# openSX70_SCHEMATIC_COMPLETE.net
KiCad netlist of a schematic drawn in EAGLE
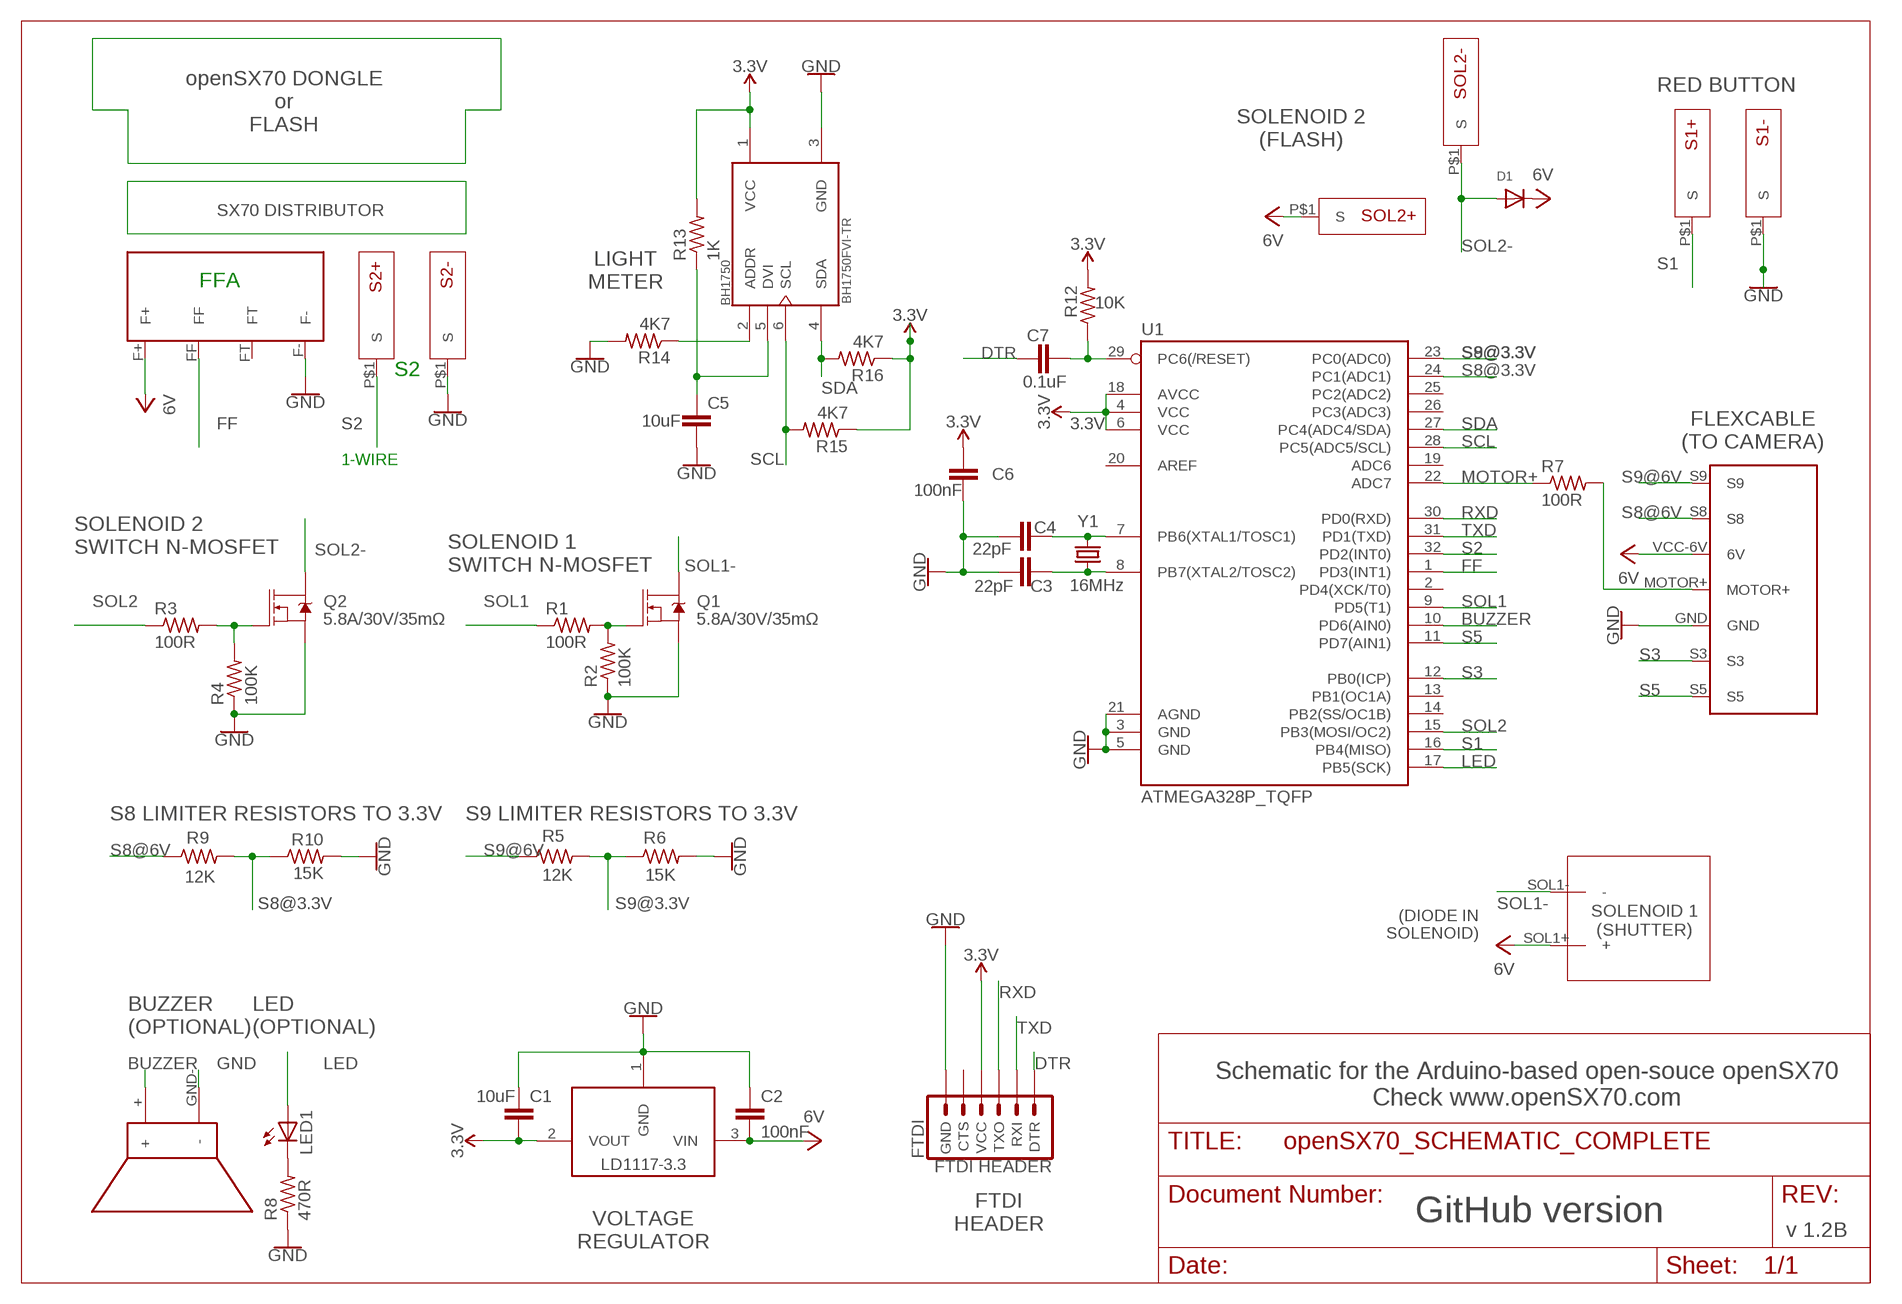
[diagram p0: schematic, sheet 1]

(export (version "E")
  (design (tool "Eeschema 10.0.6"))
  (components
    (comp (ref "BH1750")
      (value "BH1750FVI-TR")
      (footprint "eagle-import:SOTFL50P300X75-6N")
      (fields (field (name "MF") "Rohm"))
      (libsource (lib "eagle-import") (part "BH1750FVI-TR"))
    )
    (comp (ref "BUZZER")
      (value "CSET8-5G")
      (footprint "eagle-import:CSET8-5G_PACKAGE")
      (libsource (lib "eagle-import") (part "CSET8-5G"))
    )
    (comp (ref "C1")
      (value "10uF")
      (footprint "eagle-import:0603")
      (libsource (lib "eagle-import") (part "10UF-0603-6.3V-20%"))
    )
    (comp (ref "C2")
      (value "100nF")
      (footprint "eagle-import:C0603K")
      (libsource (lib "eagle-import") (part "C-EUC0603K"))
    )
    (comp (ref "C3")
      (value "22pF")
      (footprint "eagle-import:0603")
      (libsource (lib "eagle-import") (part "22PF-0603-50V-5%"))
    )
    (comp (ref "C4")
      (value "22pF")
      (footprint "eagle-import:0603")
      (libsource (lib "eagle-import") (part "22PF-0603-50V-5%"))
    )
    (comp (ref "C5")
      (value "10uF")
      (footprint "eagle-import:0603")
      (libsource (lib "eagle-import") (part "10UF-0603-6.3V-20%"))
    )
    (comp (ref "C6")
      (value "100nF")
      (footprint "eagle-import:C0805")
      (libsource (lib "eagle-import") (part "resistor_C-EUC0805"))
    )
    (comp (ref "C7")
      (value "0.1uF")
      (footprint "eagle-import:0603")
      (libsource (lib "eagle-import") (part "0.1UF-0603-25V-(+80/-20%)"))
    )
    (comp (ref "D1")
      (value "DIODESOD-523")
      (footprint "eagle-import:SOD-523")
      (libsource (lib "eagle-import") (part "DIODESOD-523"))
    )
    (comp (ref "FTDI")
      (value "FTDI HEADER")
      (footprint "eagle-import:1X06")
      (libsource (lib "eagle-import") (part "6_PIN_SERIAL_TARGET"))
    )
    (comp (ref "LD11173.3V")
      (value "LD1117 3.3V")
      (footprint "eagle-import:SOT223")
      (fields (field (name "MF") "Advanced Monolithic Systems") (field (name "MP") "AMS1117-5.0"))
      (libsource (lib "eagle-import") (part "LD1117-3.3"))
    )
    (comp (ref "LED1")
      (value "LEDCHIPLED_0805")
      (footprint "eagle-import:CHIPLED_0805")
      (libsource (lib "eagle-import") (part "LEDCHIPLED_0805"))
    )
    (comp (ref "Q1")
      (value "5.8A/30V/35mΩ")
      (footprint "eagle-import:SOT23-3")
      (libsource (lib "eagle-import") (part "MOSFET-NCH-AO3404A"))
    )
    (comp (ref "Q2")
      (value "5.8A/30V/35mΩ")
      (footprint "eagle-import:SOT23-3")
      (libsource (lib "eagle-import") (part "MOSFET-NCH-AO3404A"))
    )
    (comp (ref "R1")
      (value "100R")
      (footprint "eagle-import:R0603")
      (libsource (lib "eagle-import") (part "R-US_R0603"))
    )
    (comp (ref "R2")
      (value "100K")
      (footprint "eagle-import:R0603")
      (libsource (lib "eagle-import") (part "R-US_R0603"))
    )
    (comp (ref "R3")
      (value "100R")
      (footprint "eagle-import:R0603")
      (libsource (lib "eagle-import") (part "R-US_R0603"))
    )
    (comp (ref "R4")
      (value "100K")
      (footprint "eagle-import:R0603")
      (libsource (lib "eagle-import") (part "R-US_R0603"))
    )
    (comp (ref "R5")
      (value "12K")
      (footprint "eagle-import:R0603")
      (libsource (lib "eagle-import") (part "R-US_R0603"))
    )
    (comp (ref "R6")
      (value "15K")
      (footprint "eagle-import:R0603")
      (libsource (lib "eagle-import") (part "R-US_R0603"))
    )
    (comp (ref "R7")
      (value "100R")
      (footprint "eagle-import:R0603")
      (libsource (lib "eagle-import") (part "R-US_R0603"))
    )
    (comp (ref "R8")
      (value "470R")
      (footprint "eagle-import:R0603")
      (libsource (lib "eagle-import") (part "R-US_R0603"))
    )
    (comp (ref "R9")
      (value "12K")
      (footprint "eagle-import:R0603")
      (libsource (lib "eagle-import") (part "R-US_R0603"))
    )
    (comp (ref "R10")
      (value "15K")
      (footprint "eagle-import:R0603")
      (libsource (lib "eagle-import") (part "R-US_R0603"))
    )
    (comp (ref "R12")
      (value "10K")
      (footprint "eagle-import:R0603")
      (libsource (lib "eagle-import") (part "R-US_R0603"))
    )
    (comp (ref "R13")
      (value "1K")
      (footprint "eagle-import:R0603")
      (libsource (lib "eagle-import") (part "R-US_R0603"))
    )
    (comp (ref "R14")
      (value "4K7")
      (footprint "eagle-import:R0603")
      (libsource (lib "eagle-import") (part "R-US_R0603"))
    )
    (comp (ref "R15")
      (value "4K7")
      (footprint "eagle-import:R0603")
      (libsource (lib "eagle-import") (part "R-US_R0603"))
    )
    (comp (ref "R16")
      (value "4K7")
      (footprint "eagle-import:R0603")
      (libsource (lib "eagle-import") (part "R-US_R0603"))
    )
    (comp (ref "S1+")
      (value "SX70-S-PAD-NEW")
      (footprint "eagle-import:SX70-S-PAD2")
      (libsource (lib "eagle-import") (part "SX70-S-PAD-NEW"))
    )
    (comp (ref "S1-")
      (value "SX70-S-PAD-NEW")
      (footprint "eagle-import:SX70-S-PAD2")
      (libsource (lib "eagle-import") (part "SX70-S-PAD-NEW"))
    )
    (comp (ref "S2+")
      (value "SX70-S-PAD-NEW")
      (footprint "eagle-import:SX70-S-PAD2")
      (libsource (lib "eagle-import") (part "SX70-S-PAD-NEW"))
    )
    (comp (ref "S2-")
      (value "SX70-S-PAD-NEW")
      (footprint "eagle-import:SX70-S-PAD2")
      (libsource (lib "eagle-import") (part "SX70-S-PAD-NEW"))
    )
    (comp (ref "SOL1")
      (value "SX70-SOLENOID1-2PADS")
      (footprint "eagle-import:SX70-SOLENOID1-2")
      (libsource (lib "eagle-import") (part "SX70-SOLENOID1-2PADS"))
    )
    (comp (ref "SOL2+")
      (value "SX70-S-PAD-NEW")
      (footprint "eagle-import:SX70-S-PAD2")
      (libsource (lib "eagle-import") (part "SX70-S-PAD-NEW"))
    )
    (comp (ref "SOL2-")
      (value "SX70-S-PAD-NEW")
      (footprint "eagle-import:SX70-S-PAD2")
      (libsource (lib "eagle-import") (part "SX70-S-PAD-NEW"))
    )
    (comp (ref "U$1")
      (value "SX70-7-PAD")
      (footprint "eagle-import:SX70-7-PAD")
      (libsource (lib "eagle-import") (part "SX70-7-PAD"))
    )
    (comp (ref "U$2")
      (value "SX70-FFA-PAD")
      (footprint "eagle-import:FFA-PAD-PACKAGE")
      (libsource (lib "eagle-import") (part "SX70-FFA-PAD"))
    )
    (comp (ref "U1")
      (value "ATMEGA328P_TQFP")
      (footprint "eagle-import:TQFP32-08")
      (libsource (lib "eagle-import") (part "ATMEGA328P_TQFP"))
    )
    (comp (ref "Y1")
      (value "16MHz")
      (footprint "eagle-import:CRYSTAL-SMD-5X3.2-4PAD")
      (libsource (lib "eagle-import") (part "CRYSTAL-16MHZSMD-5X3.2"))
    )
  )
  (nets
    (net (code "1") (name "/BUZZER") (class "Default")
      (node (ref "BUZZER") (pin "+") (pinfunction "+_+") (pintype "bidirectional"))
      (node (ref "U1") (pin "10") (pinfunction "PD6(AIN0)_10") (pintype "bidirectional"))
    )
    (net (code "2") (name "/DTR") (class "Default")
      (node (ref "C7") (pin "1") (pinfunction "1_1") (pintype "passive"))
      (node (ref "FTDI") (pin "1") (pinfunction "DTR_1") (pintype "passive"))
    )
    (net (code "3") (name "/FF") (class "Default")
      (node (ref "U$2") (pin "FF") (pinfunction "FF_FF") (pintype "bidirectional"))
      (node (ref "U1") (pin "1") (pinfunction "PD3(INT1)_1") (pintype "bidirectional"))
    )
    (net (code "4") (name "/LED") (class "Default")
      (node (ref "LED1") (pin "A") (pinfunction "A_A") (pintype "passive"))
      (node (ref "U1") (pin "17") (pinfunction "PB5(SCK)_17") (pintype "bidirectional"))
    )
    (net (code "5") (name "/MOTOR+") (class "Default")
      (node (ref "R7") (pin "1") (pinfunction "1_1") (pintype "passive"))
      (node (ref "U1") (pin "22") (pinfunction "ADC7_22") (pintype "bidirectional"))
    )
    (net (code "6") (name "/RXD") (class "Default")
      (node (ref "FTDI") (pin "3") (pinfunction "TXO_3") (pintype "passive"))
      (node (ref "U1") (pin "30") (pinfunction "PD0(RXD)_30") (pintype "bidirectional"))
    )
    (net (code "7") (name "/S1") (class "Default")
      (node (ref "S1+") (pin "P$1") (pinfunction "S_P$1") (pintype "bidirectional"))
      (node (ref "U1") (pin "16") (pinfunction "PB4(MISO)_16") (pintype "bidirectional"))
    )
    (net (code "8") (name "/S2") (class "Default")
      (node (ref "S2+") (pin "P$1") (pinfunction "S_P$1") (pintype "bidirectional"))
      (node (ref "U1") (pin "32") (pinfunction "PD2(INT0)_32") (pintype "bidirectional"))
    )
    (net (code "9") (name "/S3") (class "Default")
      (node (ref "U$1") (pin "S3") (pinfunction "S3_S3") (pintype "bidirectional"))
      (node (ref "U1") (pin "12") (pinfunction "PB0(ICP)_12") (pintype "bidirectional"))
    )
    (net (code "10") (name "/S5") (class "Default")
      (node (ref "U$1") (pin "S5") (pinfunction "S5_S5") (pintype "bidirectional"))
      (node (ref "U1") (pin "11") (pinfunction "PD7(AIN1)_11") (pintype "bidirectional"))
    )
    (net (code "11") (name "/S8@3.3V") (class "Default")
      (node (ref "R10") (pin "1") (pinfunction "1_1") (pintype "passive"))
      (node (ref "R9") (pin "2") (pinfunction "2_2") (pintype "passive"))
      (node (ref "U1") (pin "24") (pinfunction "PC1(ADC1)_24") (pintype "bidirectional"))
    )
    (net (code "12") (name "/S8@6V") (class "Default")
      (node (ref "R9") (pin "1") (pinfunction "1_1") (pintype "passive"))
      (node (ref "U$1") (pin "S8") (pinfunction "S8_S8") (pintype "bidirectional"))
    )
    (net (code "13") (name "/S9@3.3V") (class "Default")
      (node (ref "R5") (pin "2") (pinfunction "2_2") (pintype "passive"))
      (node (ref "R6") (pin "1") (pinfunction "1_1") (pintype "passive"))
      (node (ref "U1") (pin "23") (pinfunction "PC0(ADC0)_23") (pintype "bidirectional"))
    )
    (net (code "14") (name "/S9@6V") (class "Default")
      (node (ref "R5") (pin "1") (pinfunction "1_1") (pintype "passive"))
      (node (ref "U$1") (pin "S9") (pinfunction "S9_S9") (pintype "bidirectional"))
    )
    (net (code "15") (name "/SCL") (class "Default")
      (node (ref "BH1750") (pin "6") (pinfunction "SCL_6") (pintype "input"))
      (node (ref "R15") (pin "2") (pinfunction "2_2") (pintype "passive"))
      (node (ref "U1") (pin "28") (pinfunction "PC5(ADC5/SCL)_28") (pintype "bidirectional"))
    )
    (net (code "16") (name "/SDA") (class "Default")
      (node (ref "BH1750") (pin "4") (pinfunction "SDA_4") (pintype "bidirectional"))
      (node (ref "R16") (pin "2") (pinfunction "2_2") (pintype "passive"))
      (node (ref "U1") (pin "27") (pinfunction "PC4(ADC4/SDA)_27") (pintype "bidirectional"))
    )
    (net (code "17") (name "/SOL1") (class "Default")
      (node (ref "R1") (pin "1") (pinfunction "1_1") (pintype "passive"))
      (node (ref "U1") (pin "9") (pinfunction "PD5(T1)_9") (pintype "bidirectional"))
    )
    (net (code "18") (name "/SOL1-") (class "Default")
      (node (ref "Q1") (pin "3") (pinfunction "D_3") (pintype "bidirectional"))
      (node (ref "SOL1") (pin "SOL1-") (pinfunction "-_SOL1-") (pintype "bidirectional"))
    )
    (net (code "19") (name "/SOL2") (class "Default")
      (node (ref "R3") (pin "1") (pinfunction "1_1") (pintype "passive"))
      (node (ref "U1") (pin "15") (pinfunction "PB3(MOSI/OC2)_15") (pintype "bidirectional"))
    )
    (net (code "20") (name "/SOL2-") (class "Default")
      (node (ref "D1") (pin "A") (pinfunction "A_A") (pintype "passive"))
      (node (ref "Q2") (pin "3") (pinfunction "D_3") (pintype "bidirectional"))
      (node (ref "SOL2-") (pin "P$1") (pinfunction "S_P$1") (pintype "bidirectional"))
    )
    (net (code "21") (name "/TXD") (class "Default")
      (node (ref "FTDI") (pin "2") (pinfunction "RXI_2") (pintype "passive"))
      (node (ref "U1") (pin "31") (pinfunction "PD1(TXD)_31") (pintype "bidirectional"))
    )
    (net (code "22") (name "3.3V") (class "Default")
      (node (ref "BH1750") (pin "1") (pinfunction "VCC_1") (pintype "power_in"))
      (node (ref "C1") (pin "2") (pinfunction "2_2") (pintype "passive"))
      (node (ref "C6") (pin "1") (pinfunction "1_1") (pintype "passive"))
      (node (ref "FTDI") (pin "4") (pinfunction "VCC_4") (pintype "passive"))
      (node (ref "LD11173.3V") (pin "2") (pinfunction "VOUT_2") (pintype "bidirectional"))
      (node (ref "R12") (pin "2") (pinfunction "2_2") (pintype "passive"))
      (node (ref "R13") (pin "2") (pinfunction "2_2") (pintype "passive"))
      (node (ref "R15") (pin "1") (pinfunction "1_1") (pintype "passive"))
      (node (ref "R16") (pin "1") (pinfunction "1_1") (pintype "passive"))
      (node (ref "U1") (pin "18") (pinfunction "AVCC_18") (pintype "bidirectional"))
      (node (ref "U1") (pin "4") (pinfunction "VCC_4") (pintype "bidirectional"))
      (node (ref "U1") (pin "6") (pinfunction "VCC_6") (pintype "bidirectional"))
    )
    (net (code "23") (name "6V") (class "Default")
      (node (ref "C2") (pin "2") (pinfunction "2_2") (pintype "passive"))
      (node (ref "D1") (pin "K") (pinfunction "C_K") (pintype "passive"))
      (node (ref "LD11173.3V") (pin "3") (pinfunction "VIN_3") (pintype "bidirectional"))
      (node (ref "SOL1") (pin "SOL1+") (pinfunction "+_SOL1+") (pintype "bidirectional"))
      (node (ref "SOL2+") (pin "P$1") (pinfunction "S_P$1") (pintype "bidirectional"))
      (node (ref "U$1") (pin "VCC-6V") (pinfunction "6V_VCC-6V") (pintype "bidirectional"))
      (node (ref "U$2") (pin "F+") (pinfunction "F+_F+") (pintype "bidirectional"))
    )
    (net (code "24") (name "GND") (class "Default")
      (node (ref "BH1750") (pin "3") (pinfunction "GND_3") (pintype "power_in"))
      (node (ref "BUZZER") (pin "GND-") (pinfunction "-_GND-") (pintype "bidirectional"))
      (node (ref "C1") (pin "1") (pinfunction "1_1") (pintype "passive"))
      (node (ref "C2") (pin "1") (pinfunction "1_1") (pintype "passive"))
      (node (ref "C3") (pin "1") (pinfunction "1_1") (pintype "passive"))
      (node (ref "C4") (pin "1") (pinfunction "1_1") (pintype "passive"))
      (node (ref "C5") (pin "2") (pinfunction "2_2") (pintype "passive"))
      (node (ref "C6") (pin "2") (pinfunction "2_2") (pintype "passive"))
      (node (ref "FTDI") (pin "6") (pinfunction "GND_6") (pintype "passive"))
      (node (ref "LD11173.3V") (pin "1") (pinfunction "GND_1") (pintype "bidirectional"))
      (node (ref "Q1") (pin "2") (pinfunction "S_2") (pintype "bidirectional"))
      (node (ref "Q2") (pin "2") (pinfunction "S_2") (pintype "bidirectional"))
      (node (ref "R10") (pin "2") (pinfunction "2_2") (pintype "passive"))
      (node (ref "R14") (pin "2") (pinfunction "2_2") (pintype "passive"))
      (node (ref "R2") (pin "1") (pinfunction "1_1") (pintype "passive"))
      (node (ref "R4") (pin "1") (pinfunction "1_1") (pintype "passive"))
      (node (ref "R6") (pin "2") (pinfunction "2_2") (pintype "passive"))
      (node (ref "R8") (pin "1") (pinfunction "1_1") (pintype "passive"))
      (node (ref "S1-") (pin "P$1") (pinfunction "S_P$1") (pintype "bidirectional"))
      (node (ref "S2-") (pin "P$1") (pinfunction "S_P$1") (pintype "bidirectional"))
      (node (ref "U$1") (pin "GND") (pinfunction "GND_GND") (pintype "bidirectional"))
      (node (ref "U$2") (pin "F-") (pinfunction "F-_F-") (pintype "bidirectional"))
      (node (ref "U1") (pin "21") (pinfunction "AGND_21") (pintype "bidirectional"))
      (node (ref "U1") (pin "3") (pinfunction "GND_3") (pintype "bidirectional"))
      (node (ref "U1") (pin "5") (pinfunction "GND_5") (pintype "bidirectional"))
    )
    (net (code "25") (name "Net-(BH1750-ADDR)") (class "Default")
      (node (ref "BH1750") (pin "2") (pinfunction "ADDR_2") (pintype "input"))
      (node (ref "R14") (pin "1") (pinfunction "1_1") (pintype "passive"))
    )
    (net (code "26") (name "Net-(BH1750-DVI)") (class "Default")
      (node (ref "BH1750") (pin "5") (pinfunction "DVI_5") (pintype "input"))
      (node (ref "C5") (pin "1") (pinfunction "1_1") (pintype "passive"))
      (node (ref "R13") (pin "1") (pinfunction "1_1") (pintype "passive"))
    )
    (net (code "27") (name "Net-(LED1-PadC)") (class "Default")
      (node (ref "LED1") (pin "C") (pinfunction "C_C") (pintype "passive"))
      (node (ref "R8") (pin "2") (pinfunction "2_2") (pintype "passive"))
    )
    (net (code "28") (name "Net-(Q1-G)") (class "Default")
      (node (ref "Q1") (pin "1") (pinfunction "G_1") (pintype "bidirectional"))
      (node (ref "R1") (pin "2") (pinfunction "2_2") (pintype "passive"))
      (node (ref "R2") (pin "2") (pinfunction "2_2") (pintype "passive"))
    )
    (net (code "29") (name "Net-(Q2-G)") (class "Default")
      (node (ref "Q2") (pin "1") (pinfunction "G_1") (pintype "bidirectional"))
      (node (ref "R3") (pin "2") (pinfunction "2_2") (pintype "passive"))
      (node (ref "R4") (pin "2") (pinfunction "2_2") (pintype "passive"))
    )
    (net (code "30") (name "Net-(R7-Pad2)") (class "Default")
      (node (ref "R7") (pin "2") (pinfunction "2_2") (pintype "passive"))
      (node (ref "U$1") (pin "MOTOR+") (pinfunction "MOTOR+_MOTOR+") (pintype "bidirectional"))
    )
    (net (code "31") (name "Net-(U1-PB6(XTAL1{slash}TOSC1))") (class "Default")
      (node (ref "C4") (pin "2") (pinfunction "2_2") (pintype "passive"))
      (node (ref "U1") (pin "7") (pinfunction "PB6(XTAL1/TOSC1)_7") (pintype "bidirectional"))
      (node (ref "Y1") (pin "3") (pinfunction "2_3") (pintype "passive"))
    )
    (net (code "32") (name "Net-(U1-PB7(XTAL2{slash}TOSC2))") (class "Default")
      (node (ref "C3") (pin "2") (pinfunction "2_2") (pintype "passive"))
      (node (ref "U1") (pin "8") (pinfunction "PB7(XTAL2/TOSC2)_8") (pintype "bidirectional"))
      (node (ref "Y1") (pin "1") (pinfunction "1_1") (pintype "passive"))
    )
    (net (code "33") (name "Net-(U1-PC6({slash}RESET))") (class "Default")
      (node (ref "C7") (pin "2") (pinfunction "2_2") (pintype "passive"))
      (node (ref "R12") (pin "1") (pinfunction "1_1") (pintype "passive"))
      (node (ref "U1") (pin "29") (pinfunction "PC6(/RESET)_29") (pintype "bidirectional"))
    )
    (net (code "34") (name "unconnected-(FTDI-CTS-Pad5)") (class "Default")
      (node (ref "FTDI") (pin "5") (pinfunction "CTS_5") (pintype "passive"))
    )
    (net (code "35") (name "unconnected-(U$2-PadFT)") (class "Default")
      (node (ref "U$2") (pin "FT") (pinfunction "FT_FT") (pintype "bidirectional"))
    )
    (net (code "36") (name "unconnected-(U1-ADC6-Pad19)") (class "Default")
      (node (ref "U1") (pin "19") (pinfunction "ADC6_19") (pintype "bidirectional"))
    )
    (net (code "37") (name "unconnected-(U1-AREF-Pad20)") (class "Default")
      (node (ref "U1") (pin "20") (pinfunction "AREF_20") (pintype "bidirectional"))
    )
    (net (code "38") (name "unconnected-(U1-PB1(OC1A)-Pad13)") (class "Default")
      (node (ref "U1") (pin "13") (pinfunction "PB1(OC1A)_13") (pintype "bidirectional"))
    )
    (net (code "39") (name "unconnected-(U1-PB2(SS{slash}OC1B)-Pad14)") (class "Default")
      (node (ref "U1") (pin "14") (pinfunction "PB2(SS/OC1B)_14") (pintype "bidirectional"))
    )
    (net (code "40") (name "unconnected-(U1-PC2(ADC2)-Pad25)") (class "Default")
      (node (ref "U1") (pin "25") (pinfunction "PC2(ADC2)_25") (pintype "bidirectional"))
    )
    (net (code "41") (name "unconnected-(U1-PC3(ADC3)-Pad26)") (class "Default")
      (node (ref "U1") (pin "26") (pinfunction "PC3(ADC3)_26") (pintype "bidirectional"))
    )
    (net (code "42") (name "unconnected-(U1-PD4(XCK{slash}T0)-Pad2)") (class "Default")
      (node (ref "U1") (pin "2") (pinfunction "PD4(XCK/T0)_2") (pintype "bidirectional"))
    )
  )
)
